# Feuille_2_ESP32.net
KiCad netlist of a schematic drawn in Altium Designer
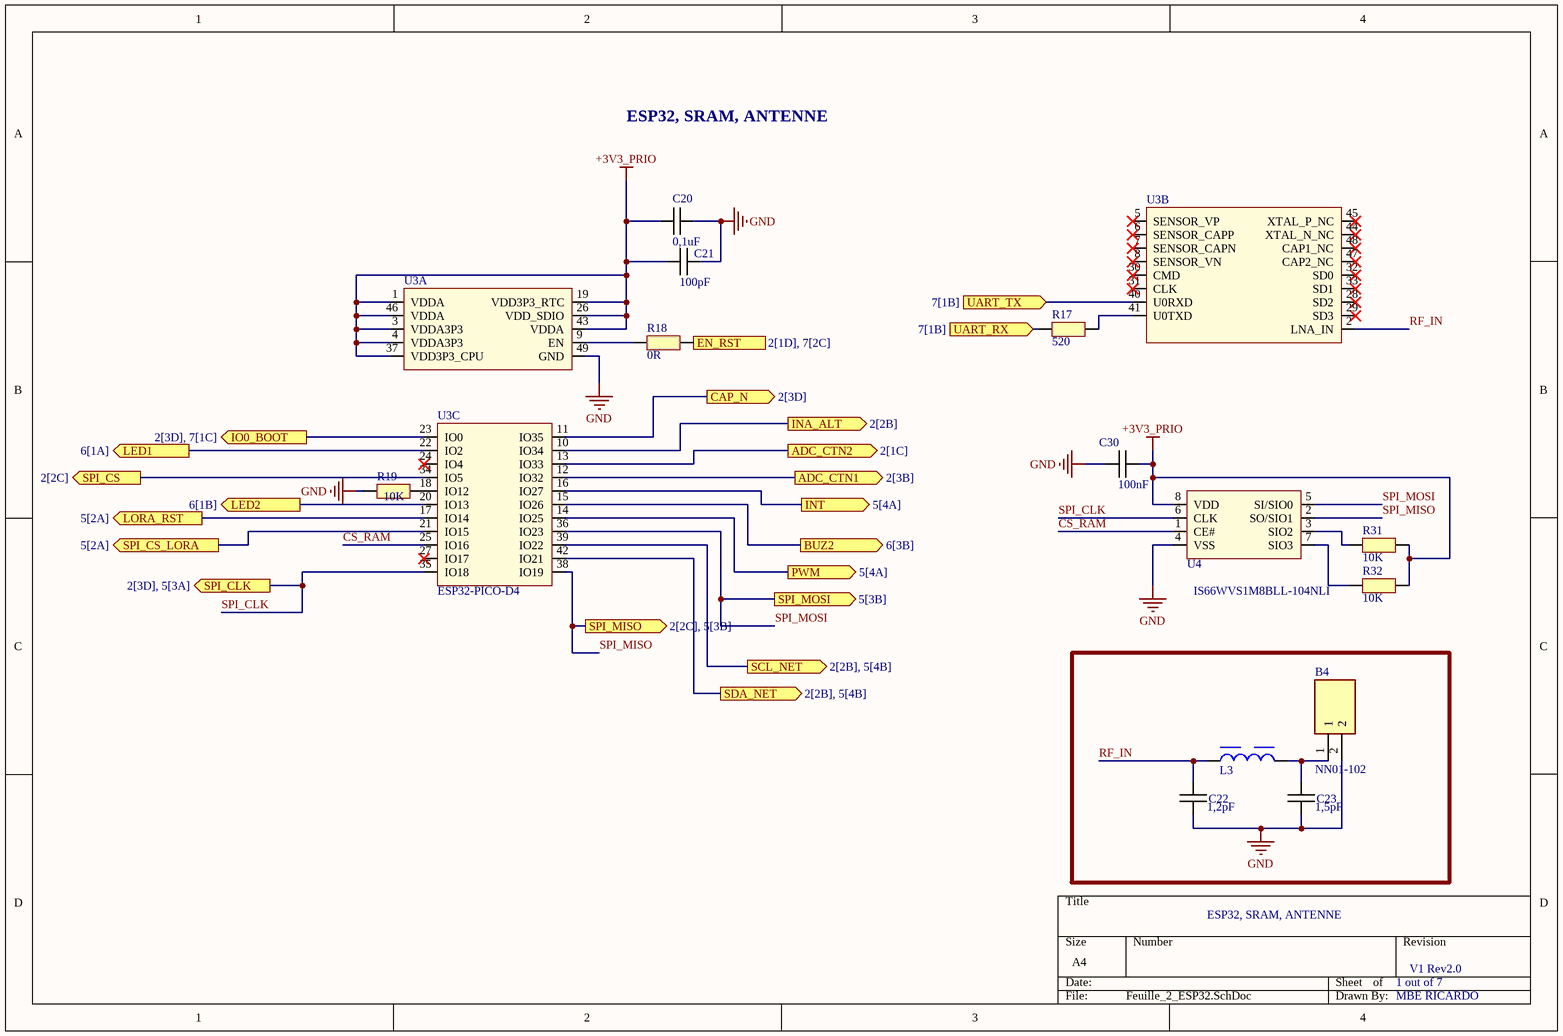
[diagram p0: Feuille_2_ESP32.SchDoc]

(export (version "E")
  (design (tool "Eeschema 10.0.6"))
  (components
    (comp (ref "B4")
      (value "NN01-102")
      (footprint "NN01-102")
      (description "Antennes Compact Reach Xtend 2.4 GHz")
      (libsource (lib "SCHLibrary") (part "NN01-102"))
    )
    (comp (ref "C20")
      (value "0,1uF")
      (footprint "CAPC1005X06N")
      (libsource (lib "SCHLibrary") (part "Capacitor"))
    )
    (comp (ref "C21")
      (value "100pF")
      (footprint "CAPC1005X06N")
      (libsource (lib "SCHLibrary") (part "Capacitor"))
    )
    (comp (ref "C22")
      (value "1,2pF")
      (footprint "CAPC1005X06N")
      (libsource (lib "SCHLibrary") (part "Capacitor"))
    )
    (comp (ref "C23")
      (value "1,5pF")
      (footprint "CAPC1005X06N")
      (libsource (lib "SCHLibrary") (part "Capacitor"))
    )
    (comp (ref "C30")
      (value "100nF")
      (footprint "CAPC1005X06N")
      (libsource (lib "SCHLibrary") (part "Capacitor"))
    )
    (comp (ref "L3")
      (value "3.3uH, 3.5A")
      (footprint "WE-LHMI_4020")
      (description "WE-LHMI SMT Power Inductor, size 4020, 3.3uH, 3.5A, 76mOhm")
      (fields
        (field (name "MANUFACTURER PART NUMBER") "74437324033")
        (field (name "MANUFACTURER") "Wurth Elektronik")
      )
      (libsource (lib "SCHLibrary") (part "74437324033"))
    )
    (comp (ref "R17")
      (value "520")
      (footprint "RESC1005X06N")
      (libsource (lib "SCHLibrary") (part "Resistor"))
    )
    (comp (ref "R18")
      (value "0R")
      (footprint "RESC1005X06N")
      (libsource (lib "SCHLibrary") (part "Resistor"))
    )
    (comp (ref "R19")
      (value "10K")
      (footprint "RESC1005X06N")
      (libsource (lib "SCHLibrary") (part "Resistor"))
    )
    (comp (ref "R31")
      (value "10K")
      (footprint "RESC1005X06N")
      (libsource (lib "SCHLibrary") (part "Resistor"))
    )
    (comp (ref "R32")
      (value "10K")
      (footprint "RESC1005X06N")
      (libsource (lib "SCHLibrary") (part "Resistor"))
    )
    (comp (ref "U3")
      (value "ESP32-PICO-D4")
      (footprint "PQFN50P700X700X104_HS-49N")
      (libsource (lib "SCHLibrary") (part "ESP32"))
    )
    (comp (ref "U4")
      (value "IS66WVS1M8BLL-104NLI")
      (footprint "SOIC127P600X175-8N")
      (description "SRAM 8Mb, SerialRAM, 2.7V-3.6V, 104MHz, 8 pin SOIC 150 mil, RoHS")
      (libsource (lib "SCHLibrary") (part "SRAM"))
    )
  )
  (nets
    (net (code "1") (name "+3V3_PRIO") (class "Default")
      (node (ref "C20") (pin "1") (pinfunction "1_1") (pintype "passive"))
      (node (ref "C21") (pin "2") (pinfunction "2_2") (pintype "passive"))
      (node (ref "C30") (pin "2") (pinfunction "2_2") (pintype "passive"))
      (node (ref "R31") (pin "1") (pinfunction "1_1") (pintype "passive"))
      (node (ref "R32") (pin "1") (pinfunction "1_1") (pintype "passive"))
      (node (ref "U3") (pin "1") (pinfunction "VDDA_1") (pintype "passive"))
      (node (ref "U3") (pin "19") (pinfunction "VDD3P3_RTC_19") (pintype "passive"))
      (node (ref "U3") (pin "26") (pinfunction "VDD_SDIO_26") (pintype "passive"))
      (node (ref "U3") (pin "3") (pinfunction "VDDA3P3_3") (pintype "passive"))
      (node (ref "U3") (pin "37") (pinfunction "VDD3P3_CPU_37") (pintype "passive"))
      (node (ref "U3") (pin "4") (pinfunction "VDDA3P3_4") (pintype "passive"))
      (node (ref "U3") (pin "43") (pinfunction "VDDA_43") (pintype "passive"))
      (node (ref "U3") (pin "46") (pinfunction "VDDA_46") (pintype "passive"))
      (node (ref "U4") (pin "8") (pinfunction "VDD_8") (pintype "passive"))
    )
    (net (code "2") (name "/ADC_CTN1") (class "Default")
      (node (ref "U3") (pin "12") (pinfunction "IO32_12") (pintype "passive"))
    )
    (net (code "3") (name "/ADC_CTN2") (class "Default")
      (node (ref "U3") (pin "13") (pinfunction "IO33_13") (pintype "passive"))
    )
    (net (code "4") (name "/BUZ2") (class "Default")
      (node (ref "U3") (pin "15") (pinfunction "IO26_15") (pintype "passive"))
    )
    (net (code "5") (name "/CAP_N") (class "Default")
      (node (ref "U3") (pin "11") (pinfunction "IO35_11") (pintype "passive"))
    )
    (net (code "6") (name "/CS_RAM") (class "Default")
      (node (ref "U3") (pin "25") (pinfunction "IO16_25") (pintype "passive"))
      (node (ref "U4") (pin "1") (pinfunction "CE#_1") (pintype "passive"))
    )
    (net (code "7") (name "/EN_RST") (class "Default")
      (node (ref "R18") (pin "1") (pinfunction "1_1") (pintype "passive"))
    )
    (net (code "8") (name "/INA_ALT") (class "Default")
      (node (ref "U3") (pin "10") (pinfunction "IO34_10") (pintype "passive"))
    )
    (net (code "9") (name "/INT") (class "Default")
      (node (ref "U3") (pin "16") (pinfunction "IO27_16") (pintype "passive"))
    )
    (net (code "10") (name "/IO0_BOOT") (class "Default")
      (node (ref "U3") (pin "23") (pinfunction "IO0_23") (pintype "passive"))
    )
    (net (code "11") (name "/LED1") (class "Default")
      (node (ref "U3") (pin "22") (pinfunction "IO2_22") (pintype "passive"))
    )
    (net (code "12") (name "/LED2") (class "Default")
      (node (ref "U3") (pin "20") (pinfunction "IO13_20") (pintype "passive"))
    )
    (net (code "13") (name "/LORA_RST") (class "Default")
      (node (ref "U3") (pin "17") (pinfunction "IO14_17") (pintype "passive"))
    )
    (net (code "14") (name "/PWM") (class "Default")
      (node (ref "U3") (pin "14") (pinfunction "IO25_14") (pintype "passive"))
    )
    (net (code "15") (name "/RF_IN") (class "Default")
      (node (ref "C22") (pin "1") (pinfunction "1_1") (pintype "passive"))
      (node (ref "L3") (pin "1") (pinfunction "1_1") (pintype "passive"))
      (node (ref "U3") (pin "2") (pinfunction "LNA_IN_2") (pintype "passive"))
    )
    (net (code "16") (name "/SCL_NET") (class "Default")
      (node (ref "U3") (pin "39") (pinfunction "IO22_39") (pintype "passive"))
    )
    (net (code "17") (name "/SDA_NET") (class "Default")
      (node (ref "U3") (pin "42") (pinfunction "IO21_42") (pintype "passive"))
    )
    (net (code "18") (name "/SPI_CLK") (class "Default")
      (node (ref "U3") (pin "35") (pinfunction "IO18_35") (pintype "passive"))
      (node (ref "U4") (pin "6") (pinfunction "CLK_6") (pintype "passive"))
    )
    (net (code "19") (name "/SPI_CS") (class "Default")
      (node (ref "U3") (pin "34") (pinfunction "IO5_34") (pintype "passive"))
    )
    (net (code "20") (name "/SPI_CS_LORA") (class "Default")
      (node (ref "U3") (pin "21") (pinfunction "IO15_21") (pintype "passive"))
    )
    (net (code "21") (name "/SPI_MISO") (class "Default")
      (node (ref "U3") (pin "38") (pinfunction "IO19_38") (pintype "passive"))
      (node (ref "U4") (pin "2") (pinfunction "SO/SIO1_2") (pintype "passive"))
    )
    (net (code "22") (name "/SPI_MOSI") (class "Default")
      (node (ref "U3") (pin "36") (pinfunction "IO23_36") (pintype "passive"))
      (node (ref "U4") (pin "5") (pinfunction "SI/SIO0_5") (pintype "passive"))
    )
    (net (code "23") (name "/UART_RX") (class "Default")
      (node (ref "R17") (pin "2") (pinfunction "2_2") (pintype "passive"))
    )
    (net (code "24") (name "/UART_TX") (class "Default")
      (node (ref "U3") (pin "40") (pinfunction "U0RXD_40") (pintype "passive"))
    )
    (net (code "25") (name "GND") (class "Default")
      (node (ref "B4") (pin "2") (pinfunction "2_2") (pintype "passive"))
      (node (ref "C20") (pin "2") (pinfunction "2_2") (pintype "passive"))
      (node (ref "C21") (pin "1") (pinfunction "1_1") (pintype "passive"))
      (node (ref "C22") (pin "2") (pinfunction "2_2") (pintype "passive"))
      (node (ref "C23") (pin "2") (pinfunction "2_2") (pintype "passive"))
      (node (ref "C30") (pin "1") (pinfunction "1_1") (pintype "passive"))
      (node (ref "R19") (pin "2") (pinfunction "2_2") (pintype "passive"))
      (node (ref "U3") (pin "49") (pinfunction "GND_49") (pintype "passive"))
      (node (ref "U4") (pin "4") (pinfunction "VSS_4") (pintype "passive"))
    )
    (net (code "26") (name "Net-(B4-Pad1)") (class "Default")
      (node (ref "B4") (pin "1") (pinfunction "1_1") (pintype "passive"))
      (node (ref "C23") (pin "1") (pinfunction "1_1") (pintype "passive"))
      (node (ref "L3") (pin "2") (pinfunction "2_2") (pintype "passive"))
    )
    (net (code "27") (name "Net-(U3A-EN)") (class "Default")
      (node (ref "R18") (pin "2") (pinfunction "2_2") (pintype "passive"))
      (node (ref "U3") (pin "9") (pinfunction "EN_9") (pintype "passive"))
    )
    (net (code "28") (name "Net-(U3B-U0TXD)") (class "Default")
      (node (ref "R17") (pin "1") (pinfunction "1_1") (pintype "passive"))
      (node (ref "U3") (pin "41") (pinfunction "U0TXD_41") (pintype "passive"))
    )
    (net (code "29") (name "Net-(U3C-IO12)") (class "Default")
      (node (ref "R19") (pin "1") (pinfunction "1_1") (pintype "passive"))
      (node (ref "U3") (pin "18") (pinfunction "IO12_18") (pintype "passive"))
    )
    (net (code "30") (name "Net-(U4-SIO2)") (class "Default")
      (node (ref "R31") (pin "2") (pinfunction "2_2") (pintype "passive"))
      (node (ref "U4") (pin "3") (pinfunction "SIO2_3") (pintype "passive"))
    )
    (net (code "31") (name "Net-(U4-SIO3)") (class "Default")
      (node (ref "R32") (pin "2") (pinfunction "2_2") (pintype "passive"))
      (node (ref "U4") (pin "7") (pinfunction "SIO3_7") (pintype "passive"))
    )
    (net (code "32") (name "unconnected-(U3B-CAP1_NC-Pad48)") (class "Default")
      (node (ref "U3") (pin "48") (pinfunction "CAP1_NC_48") (pintype "passive+no_connect"))
    )
    (net (code "33") (name "unconnected-(U3B-CAP2_NC-Pad47)") (class "Default")
      (node (ref "U3") (pin "47") (pinfunction "CAP2_NC_47") (pintype "passive+no_connect"))
    )
    (net (code "34") (name "unconnected-(U3B-CLK-Pad31)") (class "Default")
      (node (ref "U3") (pin "31") (pinfunction "CLK_31") (pintype "passive+no_connect"))
    )
    (net (code "35") (name "unconnected-(U3B-CMD-Pad30)") (class "Default")
      (node (ref "U3") (pin "30") (pinfunction "CMD_30") (pintype "passive+no_connect"))
    )
    (net (code "36") (name "unconnected-(U3B-SD0-Pad32)") (class "Default")
      (node (ref "U3") (pin "32") (pinfunction "SD0_32") (pintype "passive+no_connect"))
    )
    (net (code "37") (name "unconnected-(U3B-SD1-Pad33)") (class "Default")
      (node (ref "U3") (pin "33") (pinfunction "SD1_33") (pintype "passive+no_connect"))
    )
    (net (code "38") (name "unconnected-(U3B-SD2-Pad28)") (class "Default")
      (node (ref "U3") (pin "28") (pinfunction "SD2_28") (pintype "passive+no_connect"))
    )
    (net (code "39") (name "unconnected-(U3B-SD3-Pad29)") (class "Default")
      (node (ref "U3") (pin "29") (pinfunction "SD3_29") (pintype "passive+no_connect"))
    )
    (net (code "40") (name "unconnected-(U3B-SENSOR_CAPN-Pad7)") (class "Default")
      (node (ref "U3") (pin "7") (pinfunction "SENSOR_CAPN_7") (pintype "passive+no_connect"))
    )
    (net (code "41") (name "unconnected-(U3B-SENSOR_CAPP-Pad6)") (class "Default")
      (node (ref "U3") (pin "6") (pinfunction "SENSOR_CAPP_6") (pintype "passive+no_connect"))
    )
    (net (code "42") (name "unconnected-(U3B-SENSOR_VN-Pad8)") (class "Default")
      (node (ref "U3") (pin "8") (pinfunction "SENSOR_VN_8") (pintype "passive+no_connect"))
    )
    (net (code "43") (name "unconnected-(U3B-SENSOR_VP-Pad5)") (class "Default")
      (node (ref "U3") (pin "5") (pinfunction "SENSOR_VP_5") (pintype "passive+no_connect"))
    )
    (net (code "44") (name "unconnected-(U3B-XTAL_N_NC-Pad44)") (class "Default")
      (node (ref "U3") (pin "44") (pinfunction "XTAL_N_NC_44") (pintype "passive+no_connect"))
    )
    (net (code "45") (name "unconnected-(U3B-XTAL_P_NC-Pad45)") (class "Default")
      (node (ref "U3") (pin "45") (pinfunction "XTAL_P_NC_45") (pintype "passive+no_connect"))
    )
    (net (code "46") (name "unconnected-(U3C-IO4-Pad24)") (class "Default")
      (node (ref "U3") (pin "24") (pinfunction "IO4_24") (pintype "passive+no_connect"))
    )
    (net (code "47") (name "unconnected-(U3C-IO17-Pad27)") (class "Default")
      (node (ref "U3") (pin "27") (pinfunction "IO17_27") (pintype "passive+no_connect"))
    )
  )
)
